# GRLV_double_30v_v0_2.net
KiCad netlist of a schematic drawn in Altium Designer
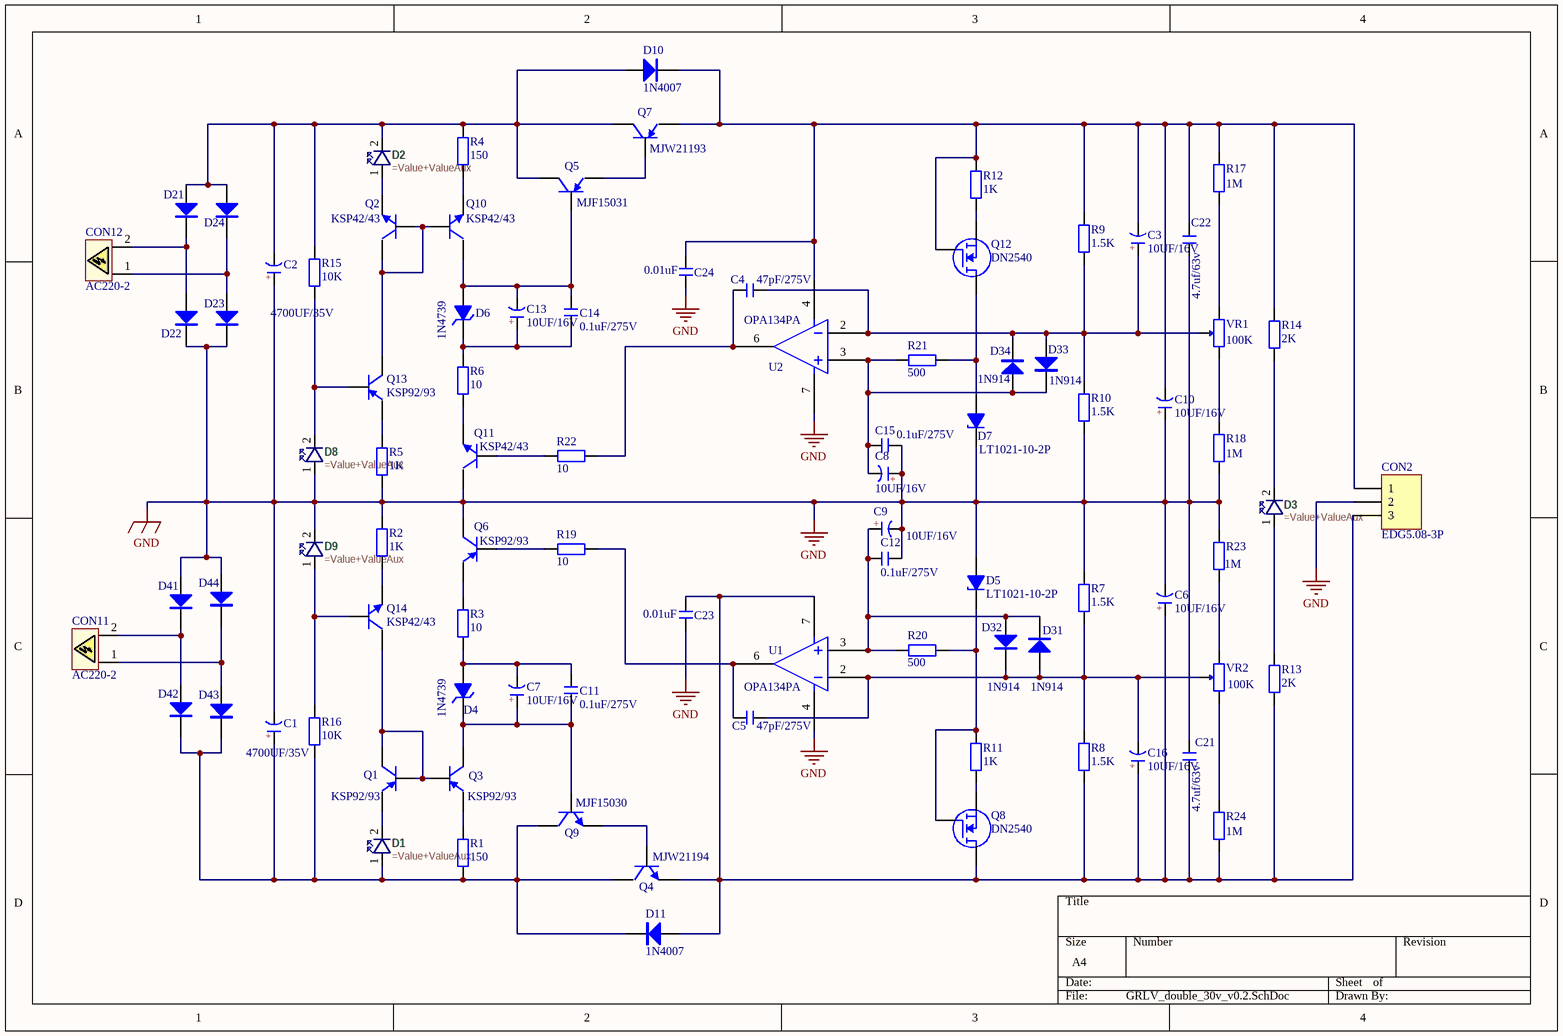
[diagram p0: GRLV_double_30v_v0.2.SchDoc]

(export (version "E")
  (design (tool "Eeschema 10.0.6"))
  (components
    (comp (ref "C1")
      (value "4700UF/35V")
      (footprint "CAP 11*35*60")
      (description "直插电解电容")
      (fields (field (name "版权归属") "源创客"))
      (libsource (lib "电阻-电容-电感") (part "C-CAP"))
    )
    (comp (ref "C2")
      (value "4700UF/35V")
      (footprint "CAP 11*35*60")
      (description "直插电解电容")
      (fields (field (name "版权归属") "源创客"))
      (libsource (lib "电阻-电容-电感") (part "C-CAP"))
    )
    (comp (ref "C3")
      (value "10UF/16V")
      (footprint "CAP 1.5*4*8")
      (description "直插电解电容")
      (fields (field (name "版权归属") "源创客"))
      (libsource (lib "电阻-电容-电感") (part "C-CAP"))
    )
    (comp (ref "C4")
      (value "47pF/275V")
      (footprint "CBB 6.3*6.3*5")
      (description "CBB电容")
      (fields (field (name "版权归属") "源创客"))
      (libsource (lib "电阻-电容-电感") (part "C-CBB"))
    )
    (comp (ref "C5")
      (value "47pF/275V")
      (footprint "CBB 6.3*6.3*5")
      (description "CBB电容")
      (fields (field (name "版权归属") "源创客"))
      (libsource (lib "电阻-电容-电感") (part "C-CBB"))
    )
    (comp (ref "C6")
      (value "10UF/16V")
      (footprint "CAP 3.5*8*11.5")
      (description "直插电解电容")
      (fields (field (name "版权归属") "源创客"))
      (libsource (lib "电阻-电容-电感") (part "C-CAP"))
    )
    (comp (ref "C7")
      (value "10UF/16V")
      (footprint "CAP 1.5*4*8")
      (description "直插电解电容")
      (fields (field (name "版权归属") "源创客"))
      (libsource (lib "电阻-电容-电感") (part "C-CAP"))
    )
    (comp (ref "C8")
      (value "10UF/16V")
      (footprint "CAP 1.5*4*8")
      (description "直插电解电容")
      (fields (field (name "版权归属") "源创客"))
      (libsource (lib "") (part "C-CAP_1"))
    )
    (comp (ref "C9")
      (value "10UF/16V")
      (footprint "CAP 1.5*4*8")
      (description "直插电解电容")
      (fields (field (name "版权归属") "源创客"))
      (libsource (lib "") (part "C-CAP_1"))
    )
    (comp (ref "C10")
      (value "10UF/16V")
      (footprint "CAP 3.5*8*11.5")
      (description "直插电解电容")
      (fields (field (name "版权归属") "源创客"))
      (libsource (lib "电阻-电容-电感") (part "C-CAP"))
    )
    (comp (ref "C11")
      (value "0.1uF/275V")
      (footprint "CBB 6.3*6.3*5")
      (description "CBB电容")
      (fields (field (name "版权归属") "源创客"))
      (libsource (lib "电阻-电容-电感") (part "C-CBB"))
    )
    (comp (ref "C12")
      (value "0.1uF/275V")
      (footprint "CBB 6.3*6.3*5")
      (description "CBB电容")
      (fields (field (name "版权归属") "源创客"))
      (libsource (lib "电阻-电容-电感") (part "C-CBB"))
    )
    (comp (ref "C13")
      (value "10UF/16V")
      (footprint "CAP 1.5*4*8")
      (description "直插电解电容")
      (fields (field (name "版权归属") "源创客"))
      (libsource (lib "电阻-电容-电感") (part "C-CAP"))
    )
    (comp (ref "C14")
      (value "0.1uF/275V")
      (footprint "CBB 6.3*6.3*5")
      (description "CBB电容")
      (fields (field (name "版权归属") "源创客"))
      (libsource (lib "电阻-电容-电感") (part "C-CBB"))
    )
    (comp (ref "C15")
      (value "0.1uF/275V")
      (footprint "CBB 6.3*6.3*5")
      (description "CBB电容")
      (fields (field (name "版权归属") "源创客"))
      (libsource (lib "电阻-电容-电感") (part "C-CBB"))
    )
    (comp (ref "C16")
      (value "10UF/16V")
      (footprint "CAP 1.5*4*8")
      (description "直插电解电容")
      (fields (field (name "版权归属") "源创客"))
      (libsource (lib "电阻-电容-电感") (part "C-CAP"))
    )
    (comp (ref "C21")
      (value "4.7uf/63v")
      (footprint "CBB 7.2*7.2*13")
      (description "MKS薄膜电容")
      (libsource (lib "电阻-电容-电感") (part "C-MKS"))
    )
    (comp (ref "C22")
      (value "4.7uf/63v")
      (footprint "CBB 7.2*7.2*13")
      (description "MKS薄膜电容")
      (libsource (lib "电阻-电容-电感") (part "C-MKS"))
    )
    (comp (ref "C23")
      (value "0.01uF")
      (footprint "CBB 6.3*6.3*5")
      (description "CBB电容")
      (fields (field (name "Comment") "0.01uF/275V") (field (name "版权归属") "源创客"))
      (libsource (lib "电阻-电容-电感") (part "C-CBB"))
    )
    (comp (ref "C24")
      (value "0.01uF")
      (footprint "CBB 6.3*6.3*5")
      (description "CBB电容")
      (fields (field (name "Comment") "0.01uF/275V") (field (name "版权归属") "源创客"))
      (libsource (lib "电阻-电容-电感") (part "C-CBB"))
    )
    (comp (ref "CON2")
      (value "EDG5.08-3P")
      (footprint "HX5.08-3S")
      (libsource (lib "Connectors") (part "EDG5.08-3P"))
    )
    (comp (ref "CON11")
      (value "AC220-2")
      (footprint "HX5.08-2L")
      (libsource (lib "Connectors") (part "AC220-2"))
    )
    (comp (ref "CON12")
      (value "AC220-2")
      (footprint "HX5.08-2L")
      (libsource (lib "Connectors") (part "AC220-2"))
    )
    (comp (ref "D1")
      (value "~")
      (footprint "LED 3MM-R")
      (description "直插式LED")
      (libsource (lib "LED") (part "LED"))
    )
    (comp (ref "D2")
      (value "~")
      (footprint "LED 3MM-R")
      (description "直插式LED")
      (libsource (lib "LED") (part "LED"))
    )
    (comp (ref "D3")
      (value "~")
      (footprint "LED 3MM-R")
      (description "直插式LED")
      (libsource (lib "LED") (part "LED"))
    )
    (comp (ref "D4")
      (value "1N4739")
      (footprint "DO-41")
      (description "9.1V/1W稳压管")
      (libsource (lib "二极管-整流桥") (part "1N4739"))
    )
    (comp (ref "D5")
      (value "LT1021-10-2P")
      (footprint "DIP8-300_MH")
      (description "10V Precision Reference 2 Pin Config")
      (libsource (lib "电压参考") (part "LT1021-10-2P"))
    )
    (comp (ref "D6")
      (value "1N4739")
      (footprint "DO-41")
      (description "9.1V/1W稳压管")
      (libsource (lib "二极管-整流桥") (part "1N4739"))
    )
    (comp (ref "D7")
      (value "LT1021-10-2P")
      (footprint "DIP8-300_MH")
      (description "10V Precision Reference 2 Pin Config")
      (libsource (lib "电压参考") (part "LT1021-10-2P"))
    )
    (comp (ref "D8")
      (value "~")
      (footprint "LED 3MM-R")
      (description "直插式LED")
      (libsource (lib "LED") (part "LED"))
    )
    (comp (ref "D9")
      (value "~")
      (footprint "LED 3MM-R")
      (description "直插式LED")
      (libsource (lib "LED") (part "LED"))
    )
    (comp (ref "D10")
      (value "1N4007")
      (footprint "DO-41")
      (description "整流二极管")
      (fields (field (name "版权归属") "源创客"))
      (libsource (lib "二极管-整流桥") (part "1N4007"))
    )
    (comp (ref "D11")
      (value "1N4007")
      (footprint "DO-41")
      (description "整流二极管")
      (fields (field (name "版权归属") "源创客"))
      (libsource (lib "二极管-整流桥") (part "1N4007"))
    )
    (comp (ref "D21")
      (value "VS-HFA08TB60-M3")
      (footprint "TO220AC")
      (description "Ultrafast Soft Recovery Diado 8A 600V")
      (libsource (lib "二极管-整流桥") (part "VS-HFA08TB60-M3"))
    )
    (comp (ref "D22")
      (value "VS-HFA08TB60-M3")
      (footprint "TO220AC")
      (description "Ultrafast Soft Recovery Diado 8A 600V")
      (libsource (lib "二极管-整流桥") (part "VS-HFA08TB60-M3"))
    )
    (comp (ref "D23")
      (value "VS-HFA08TB60-M3")
      (footprint "TO220AC")
      (description "Ultrafast Soft Recovery Diado 8A 600V")
      (libsource (lib "二极管-整流桥") (part "VS-HFA08TB60-M3"))
    )
    (comp (ref "D24")
      (value "VS-HFA08TB60-M3")
      (footprint "TO220AC")
      (description "Ultrafast Soft Recovery Diado 8A 600V")
      (libsource (lib "二极管-整流桥") (part "VS-HFA08TB60-M3"))
    )
    (comp (ref "D31")
      (value "1N914")
      (footprint "DO-35")
      (description "高速开关管 1V/0.25W")
      (libsource (lib "二极管-整流桥") (part "1N914"))
    )
    (comp (ref "D32")
      (value "1N914")
      (footprint "DO-35")
      (description "高速开关管 1V/0.25W")
      (libsource (lib "二极管-整流桥") (part "1N914"))
    )
    (comp (ref "D33")
      (value "1N914")
      (footprint "DO-35")
      (description "高速开关管 1V/0.25W")
      (libsource (lib "二极管-整流桥") (part "1N914"))
    )
    (comp (ref "D34")
      (value "1N914")
      (footprint "DO-35")
      (description "高速开关管 1V/0.25W")
      (libsource (lib "二极管-整流桥") (part "1N914"))
    )
    (comp (ref "D41")
      (value "VS-HFA08TB60-M3")
      (footprint "TO220AC")
      (description "Ultrafast Soft Recovery Diado 8A 600V")
      (libsource (lib "二极管-整流桥") (part "VS-HFA08TB60-M3"))
    )
    (comp (ref "D42")
      (value "VS-HFA08TB60-M3")
      (footprint "TO220AC")
      (description "Ultrafast Soft Recovery Diado 8A 600V")
      (libsource (lib "二极管-整流桥") (part "VS-HFA08TB60-M3"))
    )
    (comp (ref "D43")
      (value "VS-HFA08TB60-M3")
      (footprint "TO220AC")
      (description "Ultrafast Soft Recovery Diado 8A 600V")
      (libsource (lib "二极管-整流桥") (part "VS-HFA08TB60-M3"))
    )
    (comp (ref "D44")
      (value "VS-HFA08TB60-M3")
      (footprint "TO220AC")
      (description "Ultrafast Soft Recovery Diado 8A 600V")
      (libsource (lib "二极管-整流桥") (part "VS-HFA08TB60-M3"))
    )
    (comp (ref "Q1")
      (value "KSP92/93")
      (footprint "TO92A")
      (description "High Voltage PNP Transistor")
      (libsource (lib "三极管") (part "KSP92/93"))
    )
    (comp (ref "Q2")
      (value "KSP42/43")
      (footprint "TO92A")
      (description "High Voltage NPN Transistor")
      (libsource (lib "三极管") (part "KSP42/43"))
    )
    (comp (ref "Q3")
      (value "KSP92/93")
      (footprint "TO92A")
      (description "High Voltage PNP Transistor")
      (libsource (lib "三极管") (part "KSP92/93"))
    )
    (comp (ref "Q4")
      (value "MJW21194")
      (footprint "TO247V")
      (description "Power NPN Transistor")
      (libsource (lib "三极管") (part "MJW21194"))
    )
    (comp (ref "Q5")
      (value "MJF15031")
      (footprint "TO220V")
      (description "Power PNP Transistor")
      (libsource (lib "三极管") (part "MJF15031"))
    )
    (comp (ref "Q6")
      (value "KSP92/93")
      (footprint "TO92A")
      (description "High Voltage PNP Transistor")
      (libsource (lib "三极管") (part "KSP92/93"))
    )
    (comp (ref "Q7")
      (value "MJW21193")
      (footprint "TO247V")
      (description "Power PNP Transistor")
      (libsource (lib "三极管") (part "MJW21193"))
    )
    (comp (ref "Q8")
      (value "DN2540")
      (footprint "TO92A")
      (description "N沟道耗尽型DMOS场效应管 400V/150ma")
      (libsource (lib "场效应管") (part "DN2540"))
    )
    (comp (ref "Q9")
      (value "MJF15030")
      (footprint "TO220V")
      (description "Power NPN Transistor")
      (libsource (lib "三极管") (part "MJF15030"))
    )
    (comp (ref "Q10")
      (value "KSP42/43")
      (footprint "TO92A")
      (description "High Voltage NPN Transistor")
      (libsource (lib "三极管") (part "KSP42/43"))
    )
    (comp (ref "Q11")
      (value "KSP42/43")
      (footprint "TO92A")
      (description "High Voltage NPN Transistor")
      (libsource (lib "三极管") (part "KSP42/43"))
    )
    (comp (ref "Q12")
      (value "DN2540")
      (footprint "TO92A")
      (description "N沟道耗尽型DMOS场效应管 400V/150ma")
      (libsource (lib "场效应管") (part "DN2540"))
    )
    (comp (ref "Q13")
      (value "KSP92/93")
      (footprint "TO92A")
      (description "High Voltage PNP Transistor")
      (libsource (lib "三极管") (part "KSP92/93"))
    )
    (comp (ref "Q14")
      (value "KSP42/43")
      (footprint "TO92A")
      (description "High Voltage NPN Transistor")
      (libsource (lib "三极管") (part "KSP42/43"))
    )
    (comp (ref "R1")
      (value "150")
      (footprint "RS 1/4W")
      (description "直插色环电阻")
      (fields (field (name "版权归属") "源创客"))
      (libsource (lib "电阻-电容-电感") (part "R-CRR"))
    )
    (comp (ref "R2")
      (value "1K")
      (footprint "RS 1/4W")
      (description "直插色环电阻")
      (fields (field (name "版权归属") "源创客"))
      (libsource (lib "电阻-电容-电感") (part "R-CRR"))
    )
    (comp (ref "R3")
      (value "10")
      (footprint "RS 1/4W")
      (description "直插色环电阻")
      (fields (field (name "版权归属") "源创客"))
      (libsource (lib "电阻-电容-电感") (part "R-CRR"))
    )
    (comp (ref "R4")
      (value "150")
      (footprint "RS 1/4W")
      (description "直插色环电阻")
      (fields (field (name "版权归属") "源创客"))
      (libsource (lib "电阻-电容-电感") (part "R-CRR"))
    )
    (comp (ref "R5")
      (value "1K")
      (footprint "RS 1/4W")
      (description "直插色环电阻")
      (fields (field (name "版权归属") "源创客"))
      (libsource (lib "电阻-电容-电感") (part "R-CRR"))
    )
    (comp (ref "R6")
      (value "10")
      (footprint "RS 1/4W")
      (description "直插色环电阻")
      (fields (field (name "版权归属") "源创客"))
      (libsource (lib "电阻-电容-电感") (part "R-CRR"))
    )
    (comp (ref "R7")
      (value "1.5K")
      (footprint "RS 1/4W")
      (description "直插色环电阻")
      (fields (field (name "版权归属") "源创客"))
      (libsource (lib "电阻-电容-电感") (part "R-CRR"))
    )
    (comp (ref "R8")
      (value "1.5K")
      (footprint "RS 1/4W")
      (description "直插色环电阻")
      (fields (field (name "版权归属") "源创客"))
      (libsource (lib "电阻-电容-电感") (part "R-CRR"))
    )
    (comp (ref "R9")
      (value "1.5K")
      (footprint "RS 1/4W")
      (description "直插色环电阻")
      (fields (field (name "版权归属") "源创客"))
      (libsource (lib "电阻-电容-电感") (part "R-CRR"))
    )
    (comp (ref "R10")
      (value "1.5K")
      (footprint "RS 1/4W")
      (description "直插色环电阻")
      (fields (field (name "版权归属") "源创客"))
      (libsource (lib "电阻-电容-电感") (part "R-CRR"))
    )
    (comp (ref "R11")
      (value "1K")
      (footprint "RS 1/4W")
      (description "直插色环电阻")
      (fields (field (name "版权归属") "源创客"))
      (libsource (lib "电阻-电容-电感") (part "R-CRR"))
    )
    (comp (ref "R12")
      (value "1K")
      (footprint "RS 1/4W")
      (description "直插色环电阻")
      (fields (field (name "版权归属") "源创客"))
      (libsource (lib "电阻-电容-电感") (part "R-CRR"))
    )
    (comp (ref "R13")
      (value "2K")
      (footprint "RS 1/4W")
      (description "直插色环电阻")
      (fields (field (name "版权归属") "源创客"))
      (libsource (lib "电阻-电容-电感") (part "R-CRR"))
    )
    (comp (ref "R14")
      (value "2K")
      (footprint "RS 1/4W")
      (description "直插色环电阻")
      (fields (field (name "版权归属") "源创客"))
      (libsource (lib "电阻-电容-电感") (part "R-CRR"))
    )
    (comp (ref "R15")
      (value "10K")
      (footprint "RS 1/4W")
      (description "直插色环电阻")
      (fields (field (name "版权归属") "源创客"))
      (libsource (lib "电阻-电容-电感") (part "R-CRR"))
    )
    (comp (ref "R16")
      (value "10K")
      (footprint "RS 1/4W")
      (description "直插色环电阻")
      (fields (field (name "版权归属") "源创客"))
      (libsource (lib "电阻-电容-电感") (part "R-CRR"))
    )
    (comp (ref "R17")
      (value "1M")
      (footprint "RS 1/4W")
      (description "直插色环电阻")
      (fields (field (name "版权归属") "源创客"))
      (libsource (lib "电阻-电容-电感") (part "R-CRR"))
    )
    (comp (ref "R18")
      (value "1M")
      (footprint "RS 1/4W")
      (description "直插色环电阻")
      (fields (field (name "版权归属") "源创客"))
      (libsource (lib "电阻-电容-电感") (part "R-CRR"))
    )
    (comp (ref "R19")
      (value "10")
      (footprint "RS 1/4W")
      (description "直插色环电阻")
      (fields (field (name "版权归属") "源创客"))
      (libsource (lib "电阻-电容-电感") (part "R-CRR"))
    )
    (comp (ref "R20")
      (value "500")
      (footprint "RS 1/4W")
      (description "直插色环电阻")
      (fields (field (name "版权归属") "源创客"))
      (libsource (lib "电阻-电容-电感") (part "R-CRR"))
    )
    (comp (ref "R21")
      (value "500")
      (footprint "RS 1/4W")
      (description "直插色环电阻")
      (fields (field (name "版权归属") "源创客"))
      (libsource (lib "电阻-电容-电感") (part "R-CRR"))
    )
    (comp (ref "R22")
      (value "10")
      (footprint "RS 1/4W")
      (description "直插色环电阻")
      (fields (field (name "版权归属") "源创客"))
      (libsource (lib "电阻-电容-电感") (part "R-CRR"))
    )
    (comp (ref "R23")
      (value "1M")
      (footprint "RS 1/4W")
      (description "直插色环电阻")
      (fields (field (name "版权归属") "源创客"))
      (libsource (lib "电阻-电容-电感") (part "R-CRR"))
    )
    (comp (ref "R24")
      (value "1M")
      (footprint "RS 1/4W")
      (description "直插色环电阻")
      (fields (field (name "版权归属") "源创客"))
      (libsource (lib "电阻-电容-电感") (part "R-CRR"))
    )
    (comp (ref "U1") (value "OPA134PA") (footprint "DIP8-300_MH") (libsource (lib "运放") (part "OPA134PA")))
    (comp (ref "U2") (value "OPA134PA") (footprint "DIP8-300_MH") (libsource (lib "运放") (part "OPA134PA")))
    (comp (ref "VR1")
      (value "100K")
      (footprint "RS 1/2W-VR")
      (description "直插可调电阻-顶调")
      (fields (field (name "Comment") "VR-W"))
      (libsource (lib "电阻-电容-电感") (part "VR-W"))
    )
    (comp (ref "VR2")
      (value "100K")
      (footprint "RS 1/2W-VR")
      (description "直插可调电阻-顶调")
      (fields (field (name "Comment") "VR-W"))
      (libsource (lib "电阻-电容-电感") (part "VR-W"))
    )
  )
  (nets
    (net (code "1") (name "GND") (class "Default")
      (node (ref "C1") (pin "2") (pinfunction "K_2") (pintype "passive"))
      (node (ref "C10") (pin "1") (pinfunction "A_1") (pintype "passive"))
      (node (ref "C12") (pin "2") (pinfunction "2_2") (pintype "passive"))
      (node (ref "C15") (pin "2") (pinfunction "2_2") (pintype "passive"))
      (node (ref "C2") (pin "1") (pinfunction "A_1") (pintype "passive"))
      (node (ref "C21") (pin "2") (pinfunction "2_2") (pintype "passive"))
      (node (ref "C22") (pin "1") (pinfunction "1_1") (pintype "passive"))
      (node (ref "C23") (pin "1") (pinfunction "1_1") (pintype "passive"))
      (node (ref "C24") (pin "1") (pinfunction "1_1") (pintype "passive"))
      (node (ref "C6") (pin "2") (pinfunction "K_2") (pintype "passive"))
      (node (ref "C8") (pin "1") (pinfunction "A_1") (pintype "passive"))
      (node (ref "C9") (pin "2") (pinfunction "K_2") (pintype "passive"))
      (node (ref "CON2") (pin "2") (pinfunction "2_2") (pintype "passive"))
      (node (ref "D22") (pin "1") (pinfunction "Cathode_1") (pintype "passive"))
      (node (ref "D23") (pin "1") (pinfunction "Cathode_1") (pintype "passive"))
      (node (ref "D41") (pin "2") (pinfunction "Anode_2") (pintype "passive"))
      (node (ref "D44") (pin "2") (pinfunction "Anode_2") (pintype "passive"))
      (node (ref "D5") (pin "4") (pinfunction "A_4") (pintype "passive"))
      (node (ref "D7") (pin "6") (pinfunction "K_6") (pintype "passive"))
      (node (ref "D8") (pin "1") (pinfunction "A_1") (pintype "passive"))
      (node (ref "D9") (pin "2") (pinfunction "K_2") (pintype "passive"))
      (node (ref "Q11") (pin "3") (pinfunction "C_3") (pintype "passive"))
      (node (ref "Q6") (pin "3") (pinfunction "C_3") (pintype "passive"))
      (node (ref "R10") (pin "1") (pinfunction "1_1") (pintype "passive"))
      (node (ref "R18") (pin "1") (pinfunction "1_1") (pintype "passive"))
      (node (ref "R2") (pin "2") (pinfunction "2_2") (pintype "passive"))
      (node (ref "R23") (pin "2") (pinfunction "2_2") (pintype "passive"))
      (node (ref "R5") (pin "1") (pinfunction "1_1") (pintype "passive"))
      (node (ref "R7") (pin "2") (pinfunction "2_2") (pintype "passive"))
      (node (ref "U1") (pin "4") (pinfunction "V-_4") (pintype "passive"))
      (node (ref "U2") (pin "7") (pinfunction "V+_7") (pintype "passive"))
    )
    (net (code "2") (name "Net-(C1-A)") (class "Default")
      (node (ref "C1") (pin "1") (pinfunction "A_1") (pintype "passive"))
      (node (ref "D1") (pin "1") (pinfunction "A_1") (pintype "passive"))
      (node (ref "D11") (pin "2") (pinfunction "K_2") (pintype "passive"))
      (node (ref "D42") (pin "1") (pinfunction "Cathode_1") (pintype "passive"))
      (node (ref "D43") (pin "1") (pinfunction "Cathode_1") (pintype "passive"))
      (node (ref "Q4") (pin "2") (pinfunction "C_2") (pintype "passive"))
      (node (ref "Q9") (pin "2") (pinfunction "C_2") (pintype "passive"))
      (node (ref "R1") (pin "1") (pinfunction "1_1") (pintype "passive"))
      (node (ref "R16") (pin "1") (pinfunction "1_1") (pintype "passive"))
    )
    (net (code "3") (name "Net-(C2-K)") (class "Default")
      (node (ref "C2") (pin "2") (pinfunction "K_2") (pintype "passive"))
      (node (ref "D10") (pin "1") (pinfunction "A_1") (pintype "passive"))
      (node (ref "D2") (pin "2") (pinfunction "K_2") (pintype "passive"))
      (node (ref "D21") (pin "2") (pinfunction "Anode_2") (pintype "passive"))
      (node (ref "D24") (pin "2") (pinfunction "Anode_2") (pintype "passive"))
      (node (ref "Q5") (pin "2") (pinfunction "C_2") (pintype "passive"))
      (node (ref "Q7") (pin "2") (pinfunction "C_2") (pintype "passive"))
      (node (ref "R15") (pin "2") (pinfunction "2_2") (pintype "passive"))
      (node (ref "R4") (pin "2") (pinfunction "2_2") (pintype "passive"))
    )
    (net (code "4") (name "Net-(C3-A)") (class "Default")
      (node (ref "C3") (pin "1") (pinfunction "A_1") (pintype "passive"))
      (node (ref "C4") (pin "2") (pinfunction "2_2") (pintype "passive"))
      (node (ref "D33") (pin "1") (pinfunction "A_1") (pintype "passive"))
      (node (ref "D34") (pin "2") (pinfunction "K_2") (pintype "passive"))
      (node (ref "R10") (pin "2") (pinfunction "2_2") (pintype "passive"))
      (node (ref "R9") (pin "1") (pinfunction "1_1") (pintype "passive"))
      (node (ref "U2") (pin "2") (pinfunction "-in_2") (pintype "passive"))
      (node (ref "VR1") (pin "3") (pinfunction "3_3") (pintype "passive"))
    )
    (net (code "5") (name "Net-(C7-A)") (class "Default")
      (node (ref "C11") (pin "1") (pinfunction "1_1") (pintype "passive"))
      (node (ref "C7") (pin "1") (pinfunction "A_1") (pintype "passive"))
      (node (ref "D4") (pin "2") (pinfunction "K_2") (pintype "passive"))
      (node (ref "Q3") (pin "3") (pinfunction "C_3") (pintype "passive"))
      (node (ref "Q9") (pin "1") (pinfunction "B_1") (pintype "passive"))
    )
    (net (code "6") (name "Net-(C7-K)") (class "Default")
      (node (ref "C11") (pin "2") (pinfunction "2_2") (pintype "passive"))
      (node (ref "C7") (pin "2") (pinfunction "K_2") (pintype "passive"))
      (node (ref "D4") (pin "1") (pinfunction "A_1") (pintype "passive"))
      (node (ref "R3") (pin "1") (pinfunction "1_1") (pintype "passive"))
    )
    (net (code "7") (name "Net-(C8-K)") (class "Default")
      (node (ref "C15") (pin "1") (pinfunction "1_1") (pintype "passive"))
      (node (ref "C8") (pin "2") (pinfunction "K_2") (pintype "passive"))
      (node (ref "D33") (pin "2") (pinfunction "K_2") (pintype "passive"))
      (node (ref "D34") (pin "1") (pinfunction "A_1") (pintype "passive"))
      (node (ref "R21") (pin "1") (pinfunction "1_1") (pintype "passive"))
      (node (ref "U2") (pin "3") (pinfunction "+in_3") (pintype "passive"))
    )
    (net (code "8") (name "Net-(C9-A)") (class "Default")
      (node (ref "C12") (pin "1") (pinfunction "1_1") (pintype "passive"))
      (node (ref "C9") (pin "1") (pinfunction "A_1") (pintype "passive"))
      (node (ref "D31") (pin "2") (pinfunction "K_2") (pintype "passive"))
      (node (ref "D32") (pin "1") (pinfunction "A_1") (pintype "passive"))
      (node (ref "R20") (pin "1") (pinfunction "1_1") (pintype "passive"))
      (node (ref "U1") (pin "3") (pinfunction "+in_3") (pintype "passive"))
    )
    (net (code "9") (name "Net-(C10-K)") (class "Default")
      (node (ref "C10") (pin "2") (pinfunction "K_2") (pintype "passive"))
      (node (ref "C22") (pin "2") (pinfunction "2_2") (pintype "passive"))
      (node (ref "C24") (pin "2") (pinfunction "2_2") (pintype "passive"))
      (node (ref "C3") (pin "2") (pinfunction "K_2") (pintype "passive"))
      (node (ref "CON2") (pin "1") (pinfunction "1_1") (pintype "passive"))
      (node (ref "D10") (pin "2") (pinfunction "K_2") (pintype "passive"))
      (node (ref "Q12") (pin "2") (pinfunction "G_2") (pintype "passive"))
      (node (ref "Q7") (pin "3") (pinfunction "E_3") (pintype "passive"))
      (node (ref "R12") (pin "2") (pinfunction "2_2") (pintype "passive"))
      (node (ref "R14") (pin "2") (pinfunction "2_2") (pintype "passive"))
      (node (ref "R17") (pin "2") (pinfunction "2_2") (pintype "passive"))
      (node (ref "R9") (pin "2") (pinfunction "2_2") (pintype "passive"))
      (node (ref "U2") (pin "4") (pinfunction "V-_4") (pintype "passive"))
    )
    (net (code "10") (name "Net-(C13-A)") (class "Default")
      (node (ref "C13") (pin "1") (pinfunction "A_1") (pintype "passive"))
      (node (ref "C14") (pin "1") (pinfunction "1_1") (pintype "passive"))
      (node (ref "D6") (pin "2") (pinfunction "K_2") (pintype "passive"))
      (node (ref "R6") (pin "2") (pinfunction "2_2") (pintype "passive"))
    )
    (net (code "11") (name "Net-(C13-K)") (class "Default")
      (node (ref "C13") (pin "2") (pinfunction "K_2") (pintype "passive"))
      (node (ref "C14") (pin "2") (pinfunction "2_2") (pintype "passive"))
      (node (ref "D6") (pin "1") (pinfunction "A_1") (pintype "passive"))
      (node (ref "Q10") (pin "3") (pinfunction "C_3") (pintype "passive"))
      (node (ref "Q5") (pin "1") (pinfunction "B_1") (pintype "passive"))
    )
    (net (code "12") (name "Net-(C16-A)") (class "Default")
      (node (ref "C16") (pin "1") (pinfunction "A_1") (pintype "passive"))
      (node (ref "C21") (pin "1") (pinfunction "1_1") (pintype "passive"))
      (node (ref "C23") (pin "2") (pinfunction "2_2") (pintype "passive"))
      (node (ref "C6") (pin "1") (pinfunction "A_1") (pintype "passive"))
      (node (ref "CON2") (pin "3") (pinfunction "3_3") (pintype "passive"))
      (node (ref "D11") (pin "1") (pinfunction "A_1") (pintype "passive"))
      (node (ref "Q4") (pin "3") (pinfunction "E_3") (pintype "passive"))
      (node (ref "Q8") (pin "3") (pinfunction "D_3") (pintype "passive"))
      (node (ref "R13") (pin "2") (pinfunction "2_2") (pintype "passive"))
      (node (ref "R24") (pin "1") (pinfunction "1_1") (pintype "passive"))
      (node (ref "R8") (pin "1") (pinfunction "1_1") (pintype "passive"))
      (node (ref "U1") (pin "7") (pinfunction "V+_7") (pintype "passive"))
    )
    (net (code "13") (name "Net-(C16-K)") (class "Default")
      (node (ref "C16") (pin "2") (pinfunction "K_2") (pintype "passive"))
      (node (ref "C5") (pin "2") (pinfunction "2_2") (pintype "passive"))
      (node (ref "D31") (pin "1") (pinfunction "A_1") (pintype "passive"))
      (node (ref "D32") (pin "2") (pinfunction "K_2") (pintype "passive"))
      (node (ref "R7") (pin "1") (pinfunction "1_1") (pintype "passive"))
      (node (ref "R8") (pin "2") (pinfunction "2_2") (pintype "passive"))
      (node (ref "U1") (pin "2") (pinfunction "-in_2") (pintype "passive"))
      (node (ref "VR2") (pin "3") (pinfunction "3_3") (pintype "passive"))
    )
    (net (code "14") (name "Net-(CON11-G)") (class "Default")
      (node (ref "CON11") (pin "2") (pinfunction "G_2") (pintype "passive"))
      (node (ref "D41") (pin "1") (pinfunction "Cathode_1") (pintype "passive"))
      (node (ref "D42") (pin "2") (pinfunction "Anode_2") (pintype "passive"))
    )
    (net (code "15") (name "Net-(CON11-L)") (class "Default")
      (node (ref "CON11") (pin "1") (pinfunction "L_1") (pintype "passive"))
      (node (ref "D43") (pin "2") (pinfunction "Anode_2") (pintype "passive"))
      (node (ref "D44") (pin "1") (pinfunction "Cathode_1") (pintype "passive"))
    )
    (net (code "16") (name "Net-(CON12-G)") (class "Default")
      (node (ref "CON12") (pin "2") (pinfunction "G_2") (pintype "passive"))
      (node (ref "D21") (pin "1") (pinfunction "Cathode_1") (pintype "passive"))
      (node (ref "D22") (pin "2") (pinfunction "Anode_2") (pintype "passive"))
    )
    (net (code "17") (name "Net-(CON12-L)") (class "Default")
      (node (ref "CON12") (pin "1") (pinfunction "L_1") (pintype "passive"))
      (node (ref "D23") (pin "2") (pinfunction "Anode_2") (pintype "passive"))
      (node (ref "D24") (pin "1") (pinfunction "Cathode_1") (pintype "passive"))
    )
    (net (code "18") (name "Net-(D1-K)") (class "Default")
      (node (ref "D1") (pin "2") (pinfunction "K_2") (pintype "passive"))
      (node (ref "Q1") (pin "1") (pinfunction "E_1") (pintype "passive"))
    )
    (net (code "19") (name "Net-(D2-A)") (class "Default")
      (node (ref "D2") (pin "1") (pinfunction "A_1") (pintype "passive"))
      (node (ref "Q2") (pin "1") (pinfunction "E_1") (pintype "passive"))
    )
    (net (code "20") (name "Net-(D3-A)") (class "Default")
      (node (ref "D3") (pin "1") (pinfunction "A_1") (pintype "passive"))
      (node (ref "R13") (pin "1") (pinfunction "1_1") (pintype "passive"))
    )
    (net (code "21") (name "Net-(D3-K)") (class "Default")
      (node (ref "D3") (pin "2") (pinfunction "K_2") (pintype "passive"))
      (node (ref "R14") (pin "1") (pinfunction "1_1") (pintype "passive"))
    )
    (net (code "22") (name "Net-(D5-K)") (class "Default")
      (node (ref "D5") (pin "6") (pinfunction "K_6") (pintype "passive"))
      (node (ref "Q8") (pin "2") (pinfunction "G_2") (pintype "passive"))
      (node (ref "R11") (pin "2") (pinfunction "2_2") (pintype "passive"))
      (node (ref "R20") (pin "2") (pinfunction "2_2") (pintype "passive"))
    )
    (net (code "23") (name "Net-(D7-A)") (class "Default")
      (node (ref "D7") (pin "4") (pinfunction "A_4") (pintype "passive"))
      (node (ref "Q12") (pin "3") (pinfunction "D_3") (pintype "passive"))
      (node (ref "R21") (pin "2") (pinfunction "2_2") (pintype "passive"))
    )
    (net (code "24") (name "Net-(D8-K)") (class "Default")
      (node (ref "D8") (pin "2") (pinfunction "K_2") (pintype "passive"))
      (node (ref "Q13") (pin "2") (pinfunction "B_2") (pintype "passive"))
      (node (ref "R15") (pin "1") (pinfunction "1_1") (pintype "passive"))
    )
    (net (code "25") (name "Net-(D9-A)") (class "Default")
      (node (ref "D9") (pin "1") (pinfunction "A_1") (pintype "passive"))
      (node (ref "Q14") (pin "2") (pinfunction "B_2") (pintype "passive"))
      (node (ref "R16") (pin "2") (pinfunction "2_2") (pintype "passive"))
    )
    (net (code "26") (name "Net-(Q1-B)") (class "Default")
      (node (ref "Q1") (pin "2") (pinfunction "B_2") (pintype "passive"))
      (node (ref "Q1") (pin "3") (pinfunction "C_3") (pintype "passive"))
      (node (ref "Q14") (pin "3") (pinfunction "C_3") (pintype "passive"))
      (node (ref "Q3") (pin "2") (pinfunction "B_2") (pintype "passive"))
    )
    (net (code "27") (name "Net-(Q3-E)") (class "Default")
      (node (ref "Q3") (pin "1") (pinfunction "E_1") (pintype "passive"))
      (node (ref "R1") (pin "2") (pinfunction "2_2") (pintype "passive"))
    )
    (net (code "28") (name "Net-(Q4-B)") (class "Default")
      (node (ref "Q4") (pin "1") (pinfunction "B_1") (pintype "passive"))
      (node (ref "Q9") (pin "3") (pinfunction "E_3") (pintype "passive"))
    )
    (net (code "29") (name "Net-(Q5-E)") (class "Default")
      (node (ref "Q5") (pin "3") (pinfunction "E_3") (pintype "passive"))
      (node (ref "Q7") (pin "1") (pinfunction "B_1") (pintype "passive"))
    )
    (net (code "30") (name "Net-(Q6-B)") (class "Default")
      (node (ref "Q6") (pin "2") (pinfunction "B_2") (pintype "passive"))
      (node (ref "R19") (pin "1") (pinfunction "1_1") (pintype "passive"))
    )
    (net (code "31") (name "Net-(Q6-E)") (class "Default")
      (node (ref "Q6") (pin "1") (pinfunction "E_1") (pintype "passive"))
      (node (ref "R3") (pin "2") (pinfunction "2_2") (pintype "passive"))
    )
    (net (code "32") (name "Net-(Q8-S)") (class "Default")
      (node (ref "Q8") (pin "1") (pinfunction "S_1") (pintype "passive"))
      (node (ref "R11") (pin "1") (pinfunction "1_1") (pintype "passive"))
    )
    (net (code "33") (name "Net-(Q10-B)") (class "Default")
      (node (ref "Q10") (pin "2") (pinfunction "B_2") (pintype "passive"))
      (node (ref "Q13") (pin "3") (pinfunction "C_3") (pintype "passive"))
      (node (ref "Q2") (pin "2") (pinfunction "B_2") (pintype "passive"))
      (node (ref "Q2") (pin "3") (pinfunction "C_3") (pintype "passive"))
    )
    (net (code "34") (name "Net-(Q10-E)") (class "Default")
      (node (ref "Q10") (pin "1") (pinfunction "E_1") (pintype "passive"))
      (node (ref "R4") (pin "1") (pinfunction "1_1") (pintype "passive"))
    )
    (net (code "35") (name "Net-(Q11-B)") (class "Default")
      (node (ref "Q11") (pin "2") (pinfunction "B_2") (pintype "passive"))
      (node (ref "R22") (pin "1") (pinfunction "1_1") (pintype "passive"))
    )
    (net (code "36") (name "Net-(Q11-E)") (class "Default")
      (node (ref "Q11") (pin "1") (pinfunction "E_1") (pintype "passive"))
      (node (ref "R6") (pin "1") (pinfunction "1_1") (pintype "passive"))
    )
    (net (code "37") (name "Net-(Q12-S)") (class "Default")
      (node (ref "Q12") (pin "1") (pinfunction "S_1") (pintype "passive"))
      (node (ref "R12") (pin "1") (pinfunction "1_1") (pintype "passive"))
    )
    (net (code "38") (name "Net-(Q13-E)") (class "Default")
      (node (ref "Q13") (pin "1") (pinfunction "E_1") (pintype "passive"))
      (node (ref "R5") (pin "2") (pinfunction "2_2") (pintype "passive"))
    )
    (net (code "39") (name "Net-(Q14-E)") (class "Default")
      (node (ref "Q14") (pin "1") (pinfunction "E_1") (pintype "passive"))
      (node (ref "R2") (pin "1") (pinfunction "1_1") (pintype "passive"))
    )
    (net (code "40") (name "Net-(R17-Pad1)") (class "Default")
      (node (ref "R17") (pin "1") (pinfunction "1_1") (pintype "passive"))
      (node (ref "VR1") (pin "2") (pinfunction "2_2") (pintype "passive"))
    )
    (net (code "41") (name "Net-(R18-Pad2)") (class "Default")
      (node (ref "R18") (pin "2") (pinfunction "2_2") (pintype "passive"))
      (node (ref "VR1") (pin "1") (pinfunction "1_1") (pintype "passive"))
    )
    (net (code "42") (name "Net-(R23-Pad1)") (class "Default")
      (node (ref "R23") (pin "1") (pinfunction "1_1") (pintype "passive"))
      (node (ref "VR2") (pin "2") (pinfunction "2_2") (pintype "passive"))
    )
    (net (code "43") (name "Net-(R24-Pad2)") (class "Default")
      (node (ref "R24") (pin "2") (pinfunction "2_2") (pintype "passive"))
      (node (ref "VR2") (pin "1") (pinfunction "1_1") (pintype "passive"))
    )
    (net (code "44") (name "Net-(U1-out)") (class "Default")
      (node (ref "C5") (pin "1") (pinfunction "1_1") (pintype "passive"))
      (node (ref "R19") (pin "2") (pinfunction "2_2") (pintype "passive"))
      (node (ref "U1") (pin "6") (pinfunction "out_6") (pintype "passive"))
    )
    (net (code "45") (name "Net-(U2-out)") (class "Default")
      (node (ref "C4") (pin "1") (pinfunction "1_1") (pintype "passive"))
      (node (ref "R22") (pin "2") (pinfunction "2_2") (pintype "passive"))
      (node (ref "U2") (pin "6") (pinfunction "out_6") (pintype "passive"))
    )
  )
)
